# bouton.net
KiCad netlist of a schematic drawn in EAGLE
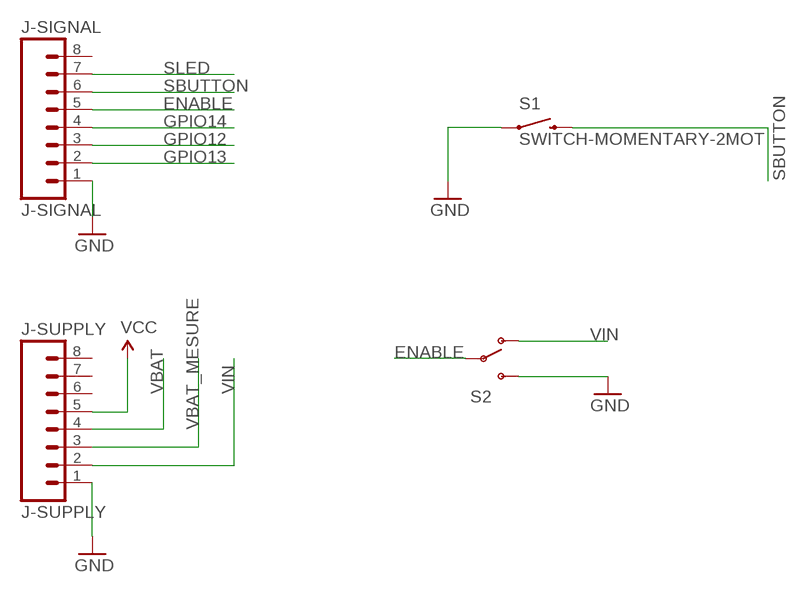
[diagram p0: schematic, sheet 1]

(export (version "E")
  (design (tool "Eeschema 10.0.6"))
  (components
    (comp (ref "J-SIGNAL")
      (value "J-SIGNAL")
      (footprint "eagle-import:1X08_ROUND")
      (libsource (lib "eagle-import") (part "M08"))
    )
    (comp (ref "J-SUPPLY")
      (value "J-SUPPLY")
      (footprint "eagle-import:1X08_ROUND")
      (libsource (lib "eagle-import") (part "M08"))
    )
    (comp (ref "S1")
      (value "SWITCH-MOMENTARY-2MOT")
      (footprint "eagle-import:TACTILE-PTH")
      (libsource (lib "eagle-import") (part "SWITCH-MOMENTARY-2MOT"))
    )
    (comp (ref "S2")
      (value "SWITCH-SPDTSMD2")
      (footprint "eagle-import:SWITCH-SPDT-SMD")
      (libsource (lib "eagle-import") (part "SWITCH-SPDTSMD2"))
    )
  )
  (nets
    (net (code "1") (name "/ENABLE") (class "Default")
      (node (ref "J-SIGNAL") (pin "5") (pinfunction "5_5") (pintype "passive"))
      (node (ref "S2") (pin "2") (pinfunction "P_2") (pintype "passive"))
    )
    (net (code "2") (name "/GPIO12") (class "Default")
      (node (ref "J-SIGNAL") (pin "3") (pinfunction "3_3") (pintype "passive"))
    )
    (net (code "3") (name "/GPIO13") (class "Default")
      (node (ref "J-SIGNAL") (pin "2") (pinfunction "2_2") (pintype "passive"))
    )
    (net (code "4") (name "/GPIO14") (class "Default")
      (node (ref "J-SIGNAL") (pin "4") (pinfunction "4_4") (pintype "passive"))
    )
    (net (code "5") (name "/SBUTTON") (class "Default")
      (node (ref "J-SIGNAL") (pin "6") (pinfunction "6_6") (pintype "passive"))
      (node (ref "S1") (pin "4") (pinfunction "2_4") (pintype "passive"))
    )
    (net (code "6") (name "/SLED") (class "Default")
      (node (ref "J-SIGNAL") (pin "7") (pinfunction "7_7") (pintype "passive"))
    )
    (net (code "7") (name "/VBAT") (class "Default")
      (node (ref "J-SUPPLY") (pin "4") (pinfunction "4_4") (pintype "passive"))
    )
    (net (code "8") (name "/VBAT_MESURE") (class "Default")
      (node (ref "J-SUPPLY") (pin "3") (pinfunction "3_3") (pintype "passive"))
    )
    (net (code "9") (name "/VIN") (class "Default")
      (node (ref "J-SUPPLY") (pin "2") (pinfunction "2_2") (pintype "passive"))
      (node (ref "S2") (pin "1") (pinfunction "O_1") (pintype "passive"))
    )
    (net (code "10") (name "GND") (class "Default")
      (node (ref "J-SIGNAL") (pin "1") (pinfunction "1_1") (pintype "passive"))
      (node (ref "J-SUPPLY") (pin "1") (pinfunction "1_1") (pintype "passive"))
      (node (ref "S1") (pin "1") (pinfunction "1_1") (pintype "passive"))
      (node (ref "S2") (pin "3") (pinfunction "S_3") (pintype "passive"))
    )
    (net (code "11") (name "VCC") (class "Default")
      (node (ref "J-SUPPLY") (pin "5") (pinfunction "5_5") (pintype "passive"))
    )
    (net (code "12") (name "unconnected-(J-SIGNAL-Pad8)") (class "Default")
      (node (ref "J-SIGNAL") (pin "8") (pinfunction "8_8") (pintype "passive"))
    )
    (net (code "13") (name "unconnected-(J-SUPPLY-Pad6)") (class "Default")
      (node (ref "J-SUPPLY") (pin "6") (pinfunction "6_6") (pintype "passive"))
    )
    (net (code "14") (name "unconnected-(J-SUPPLY-Pad7)") (class "Default")
      (node (ref "J-SUPPLY") (pin "7") (pinfunction "7_7") (pintype "passive"))
    )
    (net (code "15") (name "unconnected-(J-SUPPLY-Pad8)") (class "Default")
      (node (ref "J-SUPPLY") (pin "8") (pinfunction "8_8") (pintype "passive"))
    )
  )
)
